# DPS310_Pressure.net
KiCad netlist of a schematic drawn in EAGLE
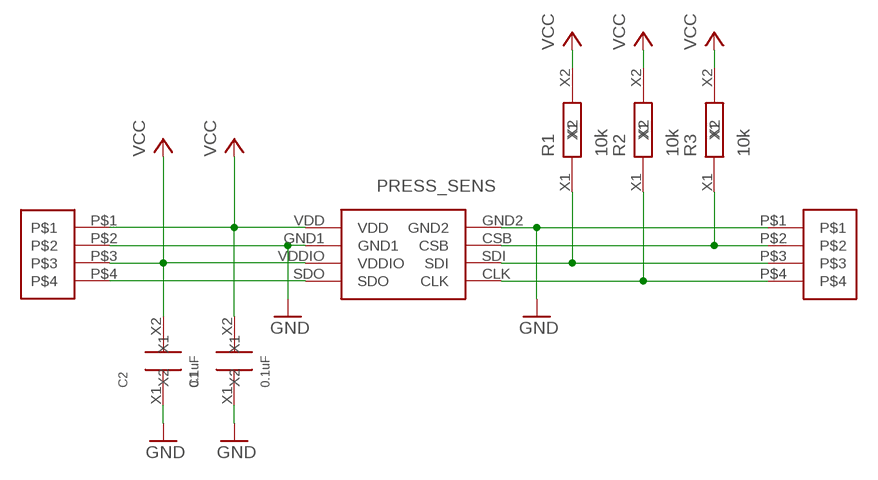
[diagram p0: schematic, sheet 1]

(export (version "E")
  (design (tool "Eeschema 10.0.6"))
  (components
    (comp (ref "C1")
      (value "0.1uF")
      (footprint "eagle-import:SMD_2.1X1.25")
      (libsource (lib "eagle-import") (part "C_SMD_2.1X1.25"))
    )
    (comp (ref "C2")
      (value "0.1uF")
      (footprint "eagle-import:SMD_2.1X1.25")
      (libsource (lib "eagle-import") (part "C_SMD_2.1X1.25"))
    )
    (comp (ref "PRESS_SENS")
      (value "DPS310_INFINEON")
      (footprint "eagle-import:DSP310")
      (libsource (lib "eagle-import") (part "DPS310_INFINEON"))
    )
    (comp (ref "R1")
      (value "10k")
      (footprint "eagle-import:SMD_2.1X1.25")
      (libsource (lib "eagle-import") (part "R_SMD_2.1X1.25"))
    )
    (comp (ref "R2")
      (value "10k")
      (footprint "eagle-import:SMD_2.1X1.25")
      (libsource (lib "eagle-import") (part "R_SMD_2.1X1.25"))
    )
    (comp (ref "R3")
      (value "10k")
      (footprint "eagle-import:SMD_2.1X1.25")
      (libsource (lib "eagle-import") (part "R_SMD_2.1X1.25"))
    )
    (comp (ref "U$1")
      (value "4-PIN-NONAME")
      (footprint "eagle-import:4-PIN-NONAME")
      (libsource (lib "eagle-import") (part "4-PIN-NONAME"))
    )
    (comp (ref "U$2")
      (value "4-PIN-NONAME")
      (footprint "eagle-import:4-PIN-NONAME")
      (libsource (lib "eagle-import") (part "4-PIN-NONAME"))
    )
  )
  (nets
    (net (code "1") (name "GND") (class "Default")
      (node (ref "C1") (pin "X1") (pinfunction "X1_X1") (pintype "bidirectional"))
      (node (ref "C2") (pin "X1") (pinfunction "X1_X1") (pintype "bidirectional"))
      (node (ref "PRESS_SENS") (pin "GND1") (pinfunction "GND1_GND1") (pintype "bidirectional"))
      (node (ref "PRESS_SENS") (pin "GND2") (pinfunction "GND2_GND2") (pintype "bidirectional"))
      (node (ref "U$1") (pin "P$1") (pinfunction "P$1_P$1") (pintype "bidirectional"))
      (node (ref "U$2") (pin "P$2") (pinfunction "P$2_P$2") (pintype "bidirectional"))
    )
    (net (code "2") (name "Net-(PRESS_SENS-PadCLK)") (class "Default")
      (node (ref "PRESS_SENS") (pin "CLK") (pinfunction "CLK_CLK") (pintype "bidirectional"))
      (node (ref "R2") (pin "X1") (pinfunction "X1_X1") (pintype "bidirectional"))
      (node (ref "U$1") (pin "P$4") (pinfunction "P$4_P$4") (pintype "bidirectional"))
    )
    (net (code "3") (name "Net-(PRESS_SENS-PadCSB)") (class "Default")
      (node (ref "PRESS_SENS") (pin "CSB") (pinfunction "CSB_CSB") (pintype "bidirectional"))
      (node (ref "R3") (pin "X1") (pinfunction "X1_X1") (pintype "bidirectional"))
      (node (ref "U$1") (pin "P$2") (pinfunction "P$2_P$2") (pintype "bidirectional"))
    )
    (net (code "4") (name "Net-(PRESS_SENS-PadSDI)") (class "Default")
      (node (ref "PRESS_SENS") (pin "SDI") (pinfunction "SDI_SDI") (pintype "bidirectional"))
      (node (ref "R1") (pin "X1") (pinfunction "X1_X1") (pintype "bidirectional"))
      (node (ref "U$1") (pin "P$3") (pinfunction "P$3_P$3") (pintype "bidirectional"))
    )
    (net (code "5") (name "Net-(PRESS_SENS-PadSDO)") (class "Default")
      (node (ref "PRESS_SENS") (pin "SDO") (pinfunction "SDO_SDO") (pintype "bidirectional"))
      (node (ref "U$2") (pin "P$4") (pinfunction "P$4_P$4") (pintype "bidirectional"))
    )
    (net (code "6") (name "VCC") (class "Default")
      (node (ref "C1") (pin "X2") (pinfunction "X2_X2") (pintype "bidirectional"))
      (node (ref "C2") (pin "X2") (pinfunction "X2_X2") (pintype "bidirectional"))
      (node (ref "PRESS_SENS") (pin "VDD") (pinfunction "VDD_VDD") (pintype "bidirectional"))
      (node (ref "PRESS_SENS") (pin "VDDIO") (pinfunction "VDDIO_VDDIO") (pintype "bidirectional"))
      (node (ref "R1") (pin "X2") (pinfunction "X2_X2") (pintype "bidirectional"))
      (node (ref "R2") (pin "X2") (pinfunction "X2_X2") (pintype "bidirectional"))
      (node (ref "R3") (pin "X2") (pinfunction "X2_X2") (pintype "bidirectional"))
      (node (ref "U$2") (pin "P$1") (pinfunction "P$1_P$1") (pintype "bidirectional"))
      (node (ref "U$2") (pin "P$3") (pinfunction "P$3_P$3") (pintype "bidirectional"))
    )
  )
)
